# BLE_SCH_Rev1.net
KiCad netlist of a schematic drawn in Altium Designer
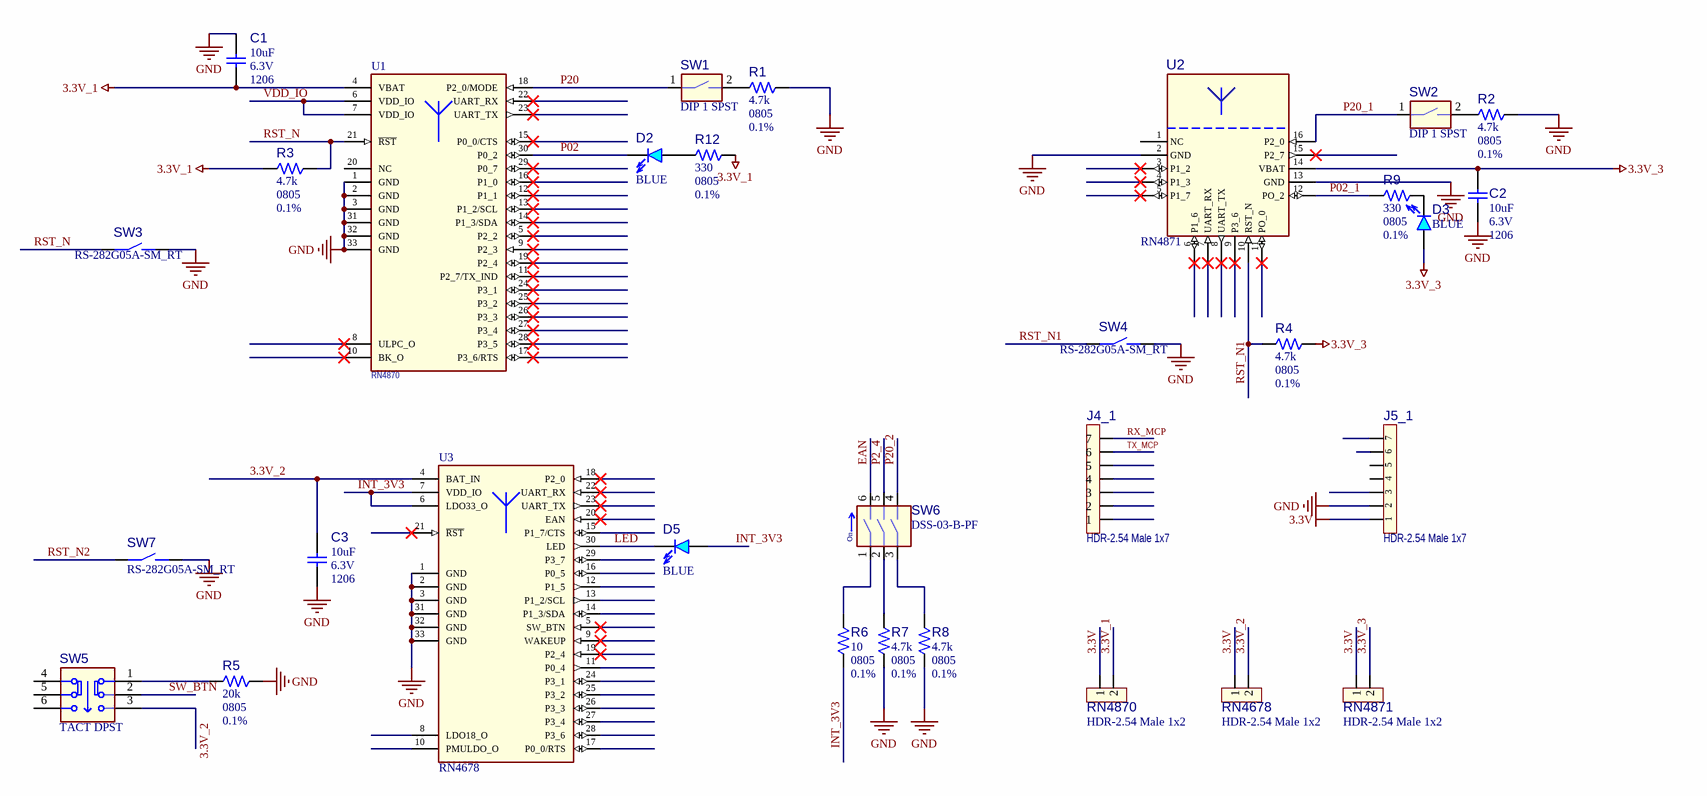
[diagram p0: BLE_SCH_Rev1.SchDoc]

(export (version "E")
  (design (tool "Eeschema 10.0.6"))
  (components
    (comp (ref "C1")
      (value "10uF")
      (footprint "CAP_C_1206")
      (fields
        (field (name "VOLTAGE") "6.3V")
        (field (name "PACKAGE") "1206")
        (field (name "TOLERANCE") "20%")
        (field (name "Comment") "Capacitor NP")
      )
      (libsource (lib "MCHP-CDB") (part "Capacitor NP"))
    )
    (comp (ref "C2")
      (value "10uF")
      (footprint "CAP_C_1206")
      (fields
        (field (name "VOLTAGE") "6.3V")
        (field (name "PACKAGE") "1206")
        (field (name "TOLERANCE") "20%")
        (field (name "Comment") "Capacitor NP")
      )
      (libsource (lib "MCHP-CDB") (part "Capacitor NP"))
    )
    (comp (ref "C3")
      (value "10uF")
      (footprint "CAP_C_1206")
      (fields
        (field (name "VOLTAGE") "6.3V")
        (field (name "PACKAGE") "1206")
        (field (name "TOLERANCE") "20%")
        (field (name "Comment") "Capacitor NP")
      )
      (libsource (lib "MCHP-CDB") (part "Capacitor NP"))
    )
    (comp (ref "D2")
      (value "BLUE")
      (footprint "LED_0805_BLUE")
      (description "LED")
      (fields (field (name "Comment") "LED_blue"))
      (libsource (lib "MCHP-CDB") (part "LED_blue"))
    )
    (comp (ref "D3")
      (value "BLUE")
      (footprint "LED_0805_BLUE")
      (description "LED")
      (fields (field (name "Comment") "LED_blue"))
      (libsource (lib "MCHP-CDB") (part "LED_blue"))
    )
    (comp (ref "D5")
      (value "BLUE")
      (footprint "LED_0805_BLUE")
      (description "LED")
      (fields (field (name "Comment") "LED_blue"))
      (libsource (lib "MCHP-CDB") (part "LED_blue"))
    )
    (comp (ref "J4_1")
      (value "HDR-2.54 Male 1x7")
      (footprint "HDR_M_2.54_1x7")
      (fields (field (name "Comment") "Header 1x7"))
      (libsource (lib "MCHP-CDB") (part "Header 1x7"))
    )
    (comp (ref "J5_1")
      (value "HDR-2.54 Male 1x7")
      (footprint "HDR_M_2.54_1x7")
      (fields (field (name "Comment") "Header 1x7"))
      (libsource (lib "") (part "Header 1x7_1"))
    )
    (comp (ref "R1")
      (value "4.7k")
      (footprint "RES_C_0805")
      (description "Resistor")
      (fields (field (name "PACKAGE") "0805") (field (name "TOLERANCE") "0.1%"))
      (libsource (lib "MCHP-CDB") (part "Resistor"))
    )
    (comp (ref "R2")
      (value "4.7k")
      (footprint "RES_C_0805")
      (description "Resistor")
      (fields (field (name "PACKAGE") "0805") (field (name "TOLERANCE") "0.1%"))
      (libsource (lib "MCHP-CDB") (part "Resistor"))
    )
    (comp (ref "R3")
      (value "4.7k")
      (footprint "RES_C_0805")
      (description "Resistor")
      (fields (field (name "PACKAGE") "0805") (field (name "TOLERANCE") "0.1%"))
      (libsource (lib "MCHP-CDB") (part "Resistor"))
    )
    (comp (ref "R4")
      (value "4.7k")
      (footprint "RES_C_0805")
      (description "Resistor")
      (fields (field (name "PACKAGE") "0805") (field (name "TOLERANCE") "0.1%"))
      (libsource (lib "MCHP-CDB") (part "Resistor"))
    )
    (comp (ref "R5")
      (value "20k")
      (footprint "RES_C_0805")
      (description "Resistor")
      (fields (field (name "PACKAGE") "0805") (field (name "TOLERANCE") "0.1%"))
      (libsource (lib "MCHP-CDB") (part "Resistor"))
    )
    (comp (ref "R6")
      (value "10")
      (footprint "RES_C_0805")
      (description "Resistor")
      (fields (field (name "PACKAGE") "0805") (field (name "TOLERANCE") "0.1%"))
      (libsource (lib "MCHP-CDB") (part "Resistor"))
    )
    (comp (ref "R7")
      (value "4.7k")
      (footprint "RES_C_0805")
      (description "Resistor")
      (fields (field (name "PACKAGE") "0805") (field (name "TOLERANCE") "0.1%"))
      (libsource (lib "MCHP-CDB") (part "Resistor"))
    )
    (comp (ref "R8")
      (value "4.7k")
      (footprint "RES_C_0805")
      (description "Resistor")
      (fields (field (name "PACKAGE") "0805") (field (name "TOLERANCE") "0.1%"))
      (libsource (lib "MCHP-CDB") (part "Resistor"))
    )
    (comp (ref "R9")
      (value "330")
      (footprint "RES_C_0805")
      (description "Resistor")
      (fields (field (name "PACKAGE") "0805") (field (name "TOLERANCE") "0.1%"))
      (libsource (lib "MCHP-CDB") (part "Resistor"))
    )
    (comp (ref "R12")
      (value "330")
      (footprint "RES_C_0805")
      (description "Resistor")
      (fields (field (name "PACKAGE") "0805") (field (name "TOLERANCE") "0.1%"))
      (libsource (lib "MCHP-CDB") (part "Resistor"))
    )
    (comp (ref "RN4678")
      (value "HDR-2.54 Male 1x2")
      (footprint "HDR_M_2.54_1x2")
      (fields (field (name "Comment") "Header 1x2") (field (name "OWNER") "Randolph Sobrepena"))
      (libsource (lib "MCHP-CDB") (part "Header 1x2"))
    )
    (comp (ref "RN4870")
      (value "HDR-2.54 Male 1x2")
      (footprint "HDR_M_2.54_1x2")
      (fields (field (name "Comment") "Header 1x2") (field (name "OWNER") "Randolph Sobrepena"))
      (libsource (lib "MCHP-CDB") (part "Header 1x2"))
    )
    (comp (ref "RN4871")
      (value "HDR-2.54 Male 1x2")
      (footprint "HDR_M_2.54_1x2")
      (fields (field (name "Comment") "Header 1x2") (field (name "OWNER") "Randolph Sobrepena"))
      (libsource (lib "MCHP-CDB") (part "Header 1x2"))
    )
    (comp (ref "SW1")
      (value "DIP 1 SPST")
      (footprint "SW_TH_2.54MM X 1 418117270901")
      (description "Switch DIP 1 Pos")
      (fields (field (name "VOLTAGE") "24V") (field (name "OWNER") "Gabor Bihari"))
      (libsource (lib "MCHP-CDB") (part "Switch DIP 1 Pos"))
    )
    (comp (ref "SW2")
      (value "DIP 1 SPST")
      (footprint "SW_TH_2.54MM X 1 418117270901")
      (description "Switch DIP 1 Pos")
      (fields (field (name "VOLTAGE") "24V") (field (name "OWNER") "Gabor Bihari"))
      (libsource (lib "MCHP-CDB") (part "Switch DIP 1 Pos"))
    )
    (comp (ref "SW3")
      (value "RS-282G05A-SM_RT")
      (footprint "SW_TACT_SMD_CK_RS-282G05A3-SM RT")
      (description "Switch")
      (fields
        (field (name "VOLTAGE") "12V")
        (field (name "Comment") "Switch 2 Pin")
        (field (name "OWNER") "Gabor Bihari")
      )
      (libsource (lib "MCHP-CDB") (part "Switch 2 Pin"))
    )
    (comp (ref "SW4")
      (value "RS-282G05A-SM_RT")
      (footprint "SW_TACT_SMD_CK_RS-282G05A3-SM RT")
      (description "Switch")
      (fields
        (field (name "VOLTAGE") "12V")
        (field (name "Comment") "Switch 2 Pin")
        (field (name "OWNER") "Gabor Bihari")
      )
      (libsource (lib "MCHP-CDB") (part "Switch 2 Pin"))
    )
    (comp (ref "SW5")
      (value "TACT DPST")
      (footprint "SW_TACT_TH_PS07-22L-PF")
      (description "PS-5177")
      (fields (field (name "Comment") "Switch on-off 6 Pin") (field (name "OWNER") "Duane Burt"))
      (libsource (lib "MCHP-CDB") (part "Switch on-off 6 Pin"))
    )
    (comp (ref "SW6")
      (value "DSS-03-B-PF")
      (footprint "SW_TH_2.54MM X 3 Omron")
      (description "Switch DIP")
      (fields (field (name "Comment") "Switch DIP 3 Pos") (field (name "OWNER") "Duane Burt"))
      (libsource (lib "MCHP-CDB") (part "Switch DIP 3 Pos"))
    )
    (comp (ref "SW7")
      (value "RS-282G05A-SM_RT")
      (footprint "SW_TACT_SMD_CK_RS-282G05A3-SM RT")
      (description "Switch")
      (fields
        (field (name "VOLTAGE") "12V")
        (field (name "Comment") "Switch 2 Pin")
        (field (name "OWNER") "Gabor Bihari")
      )
      (libsource (lib "MCHP-CDB") (part "Switch 2 Pin"))
    )
    (comp (ref "U1")
      (value "RN4870")
      (footprint "MOD_BM70BLES1FC2")
      (fields (field (name "Comment") "MODULE BM70BLES1FC2") (field (name "OWNER") "Jojie Batislaon"))
      (libsource (lib "MCHP-CDB") (part "MODULE BM70BLES1FC2"))
    )
    (comp (ref "U2")
      (value "RN4871")
      (footprint "RN4871 MODULE-16")
      (fields (field (name "Comment") "RN4871 MODULE") (field (name "OWNER") "Octavian Stroe"))
      (libsource (lib "MCHP-CDB") (part "RN4871 MODULE"))
    )
    (comp (ref "U3")
      (value "RN4678")
      (footprint "MOD_BM78SPPS5xC2")
      (fields (field (name "Comment") "MODULE BM78SPPS5xC2") (field (name "OWNER") "Jojie Batislaon"))
      (libsource (lib "MCHP-CDB") (part "MODULE BM78SPPS5xC2"))
    )
  )
  (nets
    (net (code "1") (name "/3.3V_2") (class "Default")
      (node (ref "C3") (pin "2") (pinfunction "2_2") (pintype "passive"))
      (node (ref "RN4678") (pin "2") (pinfunction "2_2") (pintype "passive"))
      (node (ref "SW5") (pin "3") (pinfunction "3_3") (pintype "passive"))
      (node (ref "U3") (pin "4") (pinfunction "BAT_IN_4") (pintype "power_in"))
    )
    (net (code "2") (name "/EAN") (class "Default")
      (node (ref "SW6") (pin "6") (pinfunction "6_6") (pintype "passive"))
    )
    (net (code "3") (name "/INT_3V3") (class "Default")
      (node (ref "D5") (pin "1") (pinfunction "A_1") (pintype "passive"))
      (node (ref "R6") (pin "2") (pinfunction "2_2") (pintype "passive"))
      (node (ref "U3") (pin "6") (pinfunction "LDO33_O_6") (pintype "power_in"))
      (node (ref "U3") (pin "7") (pinfunction "VDD_IO_7") (pintype "power_in"))
    )
    (net (code "4") (name "/LED") (class "Default")
      (node (ref "D5") (pin "2") (pinfunction "K_2") (pintype "passive"))
      (node (ref "U3") (pin "30") (pinfunction "LED_30") (pintype "output"))
    )
    (net (code "5") (name "/P02") (class "Default")
      (node (ref "D2") (pin "2") (pinfunction "K_2") (pintype "passive"))
      (node (ref "U1") (pin "30") (pinfunction "P0_2_30") (pintype "bidirectional"))
    )
    (net (code "6") (name "/P02_1") (class "Default")
      (node (ref "R9") (pin "1") (pinfunction "1_1") (pintype "passive"))
      (node (ref "U2") (pin "12") (pinfunction "PO_2_12") (pintype "bidirectional"))
    )
    (net (code "7") (name "/P2_4") (class "Default")
      (node (ref "SW6") (pin "5") (pinfunction "5_5") (pintype "passive"))
    )
    (net (code "8") (name "/P20") (class "Default")
      (node (ref "SW1") (pin "1") (pinfunction "1_1") (pintype "passive"))
      (node (ref "U1") (pin "18") (pinfunction "P2_0/MODE_18") (pintype "input"))
    )
    (net (code "9") (name "/P20_1") (class "Default")
      (node (ref "SW2") (pin "1") (pinfunction "1_1") (pintype "passive"))
      (node (ref "U2") (pin "16") (pinfunction "P2_0_16") (pintype "input"))
    )
    (net (code "10") (name "/P20_2") (class "Default")
      (node (ref "SW6") (pin "4") (pinfunction "4_4") (pintype "passive"))
    )
    (net (code "11") (name "/RST_N") (class "Default")
      (node (ref "R3") (pin "1") (pinfunction "1_1") (pintype "passive"))
      (node (ref "SW3") (pin "1") (pinfunction "1_1") (pintype "passive"))
      (node (ref "U1") (pin "21") (pinfunction "~{RST}_21") (pintype "input"))
    )
    (net (code "12") (name "/RST_N1") (class "Default")
      (node (ref "R4") (pin "2") (pinfunction "2_2") (pintype "passive"))
      (node (ref "SW4") (pin "1") (pinfunction "1_1") (pintype "passive"))
      (node (ref "U2") (pin "10") (pinfunction "RST_N_10") (pintype "input"))
    )
    (net (code "13") (name "/RST_N2") (class "Default")
      (node (ref "SW7") (pin "1") (pinfunction "1_1") (pintype "passive"))
    )
    (net (code "14") (name "/RX_MCP") (class "Default")
      (node (ref "J4_1") (pin "7") (pinfunction "7_7") (pintype "passive"))
    )
    (net (code "15") (name "/SW_BTN") (class "Default")
      (node (ref "SW5") (pin "2") (pinfunction "2_2") (pintype "passive"))
    )
    (net (code "16") (name "/TX_MCP") (class "Default")
      (node (ref "J4_1") (pin "6") (pinfunction "6_6") (pintype "passive"))
    )
    (net (code "17") (name "/VDD_IO") (class "Default")
      (node (ref "U1") (pin "6") (pinfunction "VDD_IO_6") (pintype "power_in"))
      (node (ref "U1") (pin "7") (pinfunction "VDD_IO_7") (pintype "power_in"))
    )
    (net (code "18") (name "3.3V") (class "Default")
      (node (ref "J5_1") (pin "1") (pinfunction "1_1") (pintype "passive"))
      (node (ref "RN4678") (pin "1") (pinfunction "1_1") (pintype "passive"))
      (node (ref "RN4870") (pin "1") (pinfunction "1_1") (pintype "passive"))
      (node (ref "RN4871") (pin "1") (pinfunction "1_1") (pintype "passive"))
    )
    (net (code "19") (name "3.3V_1") (class "Default")
      (node (ref "C1") (pin "1") (pinfunction "1_1") (pintype "passive"))
      (node (ref "R12") (pin "2") (pinfunction "2_2") (pintype "passive"))
      (node (ref "R3") (pin "2") (pinfunction "2_2") (pintype "passive"))
      (node (ref "RN4870") (pin "2") (pinfunction "2_2") (pintype "passive"))
      (node (ref "U1") (pin "4") (pinfunction "VBAT_4") (pintype "power_in"))
    )
    (net (code "20") (name "3.3V_3") (class "Default")
      (node (ref "C2") (pin "1") (pinfunction "1_1") (pintype "passive"))
      (node (ref "D3") (pin "1") (pinfunction "A_1") (pintype "passive"))
      (node (ref "R4") (pin "1") (pinfunction "1_1") (pintype "passive"))
      (node (ref "RN4871") (pin "2") (pinfunction "2_2") (pintype "passive"))
      (node (ref "U2") (pin "14") (pinfunction "VBAT_14") (pintype "power_in"))
    )
    (net (code "21") (name "GND") (class "Default")
      (node (ref "C1") (pin "2") (pinfunction "2_2") (pintype "passive"))
      (node (ref "C2") (pin "2") (pinfunction "2_2") (pintype "passive"))
      (node (ref "C3") (pin "1") (pinfunction "1_1") (pintype "passive"))
      (node (ref "J5_1") (pin "2") (pinfunction "2_2") (pintype "passive"))
      (node (ref "R1") (pin "1") (pinfunction "1_1") (pintype "passive"))
      (node (ref "R2") (pin "1") (pinfunction "1_1") (pintype "passive"))
      (node (ref "R5") (pin "1") (pinfunction "1_1") (pintype "passive"))
      (node (ref "R7") (pin "2") (pinfunction "2_2") (pintype "passive"))
      (node (ref "R8") (pin "2") (pinfunction "2_2") (pintype "passive"))
      (node (ref "SW3") (pin "2") (pinfunction "2_2") (pintype "passive"))
      (node (ref "SW4") (pin "2") (pinfunction "2_2") (pintype "passive"))
      (node (ref "SW7") (pin "2") (pinfunction "2_2") (pintype "passive"))
      (node (ref "U1") (pin "1") (pinfunction "GND_1") (pintype "power_in"))
      (node (ref "U1") (pin "2") (pinfunction "GND_2") (pintype "power_in"))
      (node (ref "U1") (pin "3") (pinfunction "GND_3") (pintype "power_in"))
      (node (ref "U1") (pin "31") (pinfunction "GND_31") (pintype "power_in"))
      (node (ref "U1") (pin "32") (pinfunction "GND_32") (pintype "power_in"))
      (node (ref "U1") (pin "33") (pinfunction "GND_33") (pintype "power_in"))
      (node (ref "U2") (pin "13") (pinfunction "GND_13") (pintype "power_in"))
      (node (ref "U2") (pin "2") (pinfunction "GND_2") (pintype "power_in"))
      (node (ref "U3") (pin "1") (pinfunction "GND_1") (pintype "power_in"))
      (node (ref "U3") (pin "2") (pinfunction "GND_2") (pintype "power_in"))
      (node (ref "U3") (pin "3") (pinfunction "GND_3") (pintype "power_in"))
      (node (ref "U3") (pin "31") (pinfunction "GND_31") (pintype "power_in"))
      (node (ref "U3") (pin "32") (pinfunction "GND_32") (pintype "power_in"))
      (node (ref "U3") (pin "33") (pinfunction "GND_33") (pintype "power_in"))
    )
    (net (code "22") (name "Net-(D2-A)") (class "Default")
      (node (ref "D2") (pin "1") (pinfunction "A_1") (pintype "passive"))
      (node (ref "R12") (pin "1") (pinfunction "1_1") (pintype "passive"))
    )
    (net (code "23") (name "Net-(D3-K)") (class "Default")
      (node (ref "D3") (pin "2") (pinfunction "K_2") (pintype "passive"))
      (node (ref "R9") (pin "2") (pinfunction "2_2") (pintype "passive"))
    )
    (net (code "24") (name "Net-(R1-Pad2)") (class "Default")
      (node (ref "R1") (pin "2") (pinfunction "2_2") (pintype "passive"))
      (node (ref "SW1") (pin "2") (pinfunction "2_2") (pintype "passive"))
    )
    (net (code "25") (name "Net-(R2-Pad2)") (class "Default")
      (node (ref "R2") (pin "2") (pinfunction "2_2") (pintype "passive"))
      (node (ref "SW2") (pin "2") (pinfunction "2_2") (pintype "passive"))
    )
    (net (code "26") (name "Net-(R5-Pad2)") (class "Default")
      (node (ref "R5") (pin "2") (pinfunction "2_2") (pintype "passive"))
      (node (ref "SW5") (pin "1") (pinfunction "1_1") (pintype "passive"))
    )
    (net (code "27") (name "Net-(R6-Pad1)") (class "Default")
      (node (ref "R6") (pin "1") (pinfunction "1_1") (pintype "passive"))
      (node (ref "SW6") (pin "1") (pinfunction "1_1") (pintype "passive"))
    )
    (net (code "28") (name "Net-(R7-Pad1)") (class "Default")
      (node (ref "R7") (pin "1") (pinfunction "1_1") (pintype "passive"))
      (node (ref "SW6") (pin "2") (pinfunction "2_2") (pintype "passive"))
    )
    (net (code "29") (name "Net-(R8-Pad1)") (class "Default")
      (node (ref "R8") (pin "1") (pinfunction "1_1") (pintype "passive"))
      (node (ref "SW6") (pin "3") (pinfunction "3_3") (pintype "passive"))
    )
    (net (code "30") (name "unconnected-(J4_1-Pad1)") (class "Default")
      (node (ref "J4_1") (pin "1") (pinfunction "1_1") (pintype "passive"))
    )
    (net (code "31") (name "unconnected-(J4_1-Pad2)") (class "Default")
      (node (ref "J4_1") (pin "2") (pinfunction "2_2") (pintype "passive"))
    )
    (net (code "32") (name "unconnected-(J4_1-Pad3)") (class "Default")
      (node (ref "J4_1") (pin "3") (pinfunction "3_3") (pintype "passive"))
    )
    (net (code "33") (name "unconnected-(J4_1-Pad4)") (class "Default")
      (node (ref "J4_1") (pin "4") (pinfunction "4_4") (pintype "passive"))
    )
    (net (code "34") (name "unconnected-(J4_1-Pad5)") (class "Default")
      (node (ref "J4_1") (pin "5") (pinfunction "5_5") (pintype "passive"))
    )
    (net (code "35") (name "unconnected-(J5_1-Pad3)") (class "Default")
      (node (ref "J5_1") (pin "3") (pinfunction "3_3") (pintype "passive"))
    )
    (net (code "36") (name "unconnected-(J5_1-Pad4)") (class "Default")
      (node (ref "J5_1") (pin "4") (pinfunction "4_4") (pintype "passive"))
    )
    (net (code "37") (name "unconnected-(J5_1-Pad5)") (class "Default")
      (node (ref "J5_1") (pin "5") (pinfunction "5_5") (pintype "passive"))
    )
    (net (code "38") (name "unconnected-(J5_1-Pad6)") (class "Default")
      (node (ref "J5_1") (pin "6") (pinfunction "6_6") (pintype "passive"))
    )
    (net (code "39") (name "unconnected-(J5_1-Pad7)") (class "Default")
      (node (ref "J5_1") (pin "7") (pinfunction "7_7") (pintype "passive"))
    )
    (net (code "40") (name "unconnected-(SW5-Pad4)") (class "Default")
      (node (ref "SW5") (pin "4") (pinfunction "4_4") (pintype "passive"))
    )
    (net (code "41") (name "unconnected-(SW5-Pad5)") (class "Default")
      (node (ref "SW5") (pin "5") (pinfunction "5_5") (pintype "passive"))
    )
    (net (code "42") (name "unconnected-(SW5-Pad6)") (class "Default")
      (node (ref "SW5") (pin "6") (pinfunction "6_6") (pintype "passive"))
    )
    (net (code "43") (name "unconnected-(U1-BK_O-Pad10)") (class "Default")
      (node (ref "U1") (pin "10") (pinfunction "BK_O_10") (pintype "passive+no_connect"))
    )
    (net (code "44") (name "unconnected-(U1-NC-Pad20)") (class "Default")
      (node (ref "U1") (pin "20") (pinfunction "NC_20") (pintype "passive"))
    )
    (net (code "45") (name "unconnected-(U1-P0_0{slash}CTS-Pad15)") (class "Default")
      (node (ref "U1") (pin "15") (pinfunction "P0_0/CTS_15") (pintype "bidirectional+no_connect"))
    )
    (net (code "46") (name "unconnected-(U1-P0_7-Pad29)") (class "Default")
      (node (ref "U1") (pin "29") (pinfunction "P0_7_29") (pintype "bidirectional+no_connect"))
    )
    (net (code "47") (name "unconnected-(U1-P1_0-Pad16)") (class "Default")
      (node (ref "U1") (pin "16") (pinfunction "P1_0_16") (pintype "bidirectional+no_connect"))
    )
    (net (code "48") (name "unconnected-(U1-P1_1-Pad12)") (class "Default")
      (node (ref "U1") (pin "12") (pinfunction "P1_1_12") (pintype "bidirectional+no_connect"))
    )
    (net (code "49") (name "unconnected-(U1-P1_2{slash}SCL-Pad13)") (class "Default")
      (node (ref "U1") (pin "13") (pinfunction "P1_2/SCL_13") (pintype "bidirectional+no_connect"))
    )
    (net (code "50") (name "unconnected-(U1-P1_3{slash}SDA-Pad14)") (class "Default")
      (node (ref "U1") (pin "14") (pinfunction "P1_3/SDA_14") (pintype "bidirectional+no_connect"))
    )
    (net (code "51") (name "unconnected-(U1-P2_2-Pad5)") (class "Default")
      (node (ref "U1") (pin "5") (pinfunction "P2_2_5") (pintype "bidirectional+no_connect"))
    )
    (net (code "52") (name "unconnected-(U1-P2_3-Pad9)") (class "Default")
      (node (ref "U1") (pin "9") (pinfunction "P2_3_9") (pintype "input+no_connect"))
    )
    (net (code "53") (name "unconnected-(U1-P2_4-Pad19)") (class "Default")
      (node (ref "U1") (pin "19") (pinfunction "P2_4_19") (pintype "bidirectional+no_connect"))
    )
    (net (code "54") (name "unconnected-(U1-P2_7{slash}TX_IND-Pad11)") (class "Default")
      (node (ref "U1") (pin "11") (pinfunction "P2_7/TX_IND_11") (pintype "bidirectional+no_connect"))
    )
    (net (code "55") (name "unconnected-(U1-P3_1-Pad24)") (class "Default")
      (node (ref "U1") (pin "24") (pinfunction "P3_1_24") (pintype "bidirectional+no_connect"))
    )
    (net (code "56") (name "unconnected-(U1-P3_2-Pad25)") (class "Default")
      (node (ref "U1") (pin "25") (pinfunction "P3_2_25") (pintype "bidirectional+no_connect"))
    )
    (net (code "57") (name "unconnected-(U1-P3_3-Pad26)") (class "Default")
      (node (ref "U1") (pin "26") (pinfunction "P3_3_26") (pintype "bidirectional+no_connect"))
    )
    (net (code "58") (name "unconnected-(U1-P3_4-Pad27)") (class "Default")
      (node (ref "U1") (pin "27") (pinfunction "P3_4_27") (pintype "bidirectional+no_connect"))
    )
    (net (code "59") (name "unconnected-(U1-P3_5-Pad28)") (class "Default")
      (node (ref "U1") (pin "28") (pinfunction "P3_5_28") (pintype "bidirectional+no_connect"))
    )
    (net (code "60") (name "unconnected-(U1-P3_6{slash}RTS-Pad17)") (class "Default")
      (node (ref "U1") (pin "17") (pinfunction "P3_6/RTS_17") (pintype "bidirectional+no_connect"))
    )
    (net (code "61") (name "unconnected-(U1-UART_RX-Pad22)") (class "Default")
      (node (ref "U1") (pin "22") (pinfunction "UART_RX_22") (pintype "input+no_connect"))
    )
    (net (code "62") (name "unconnected-(U1-UART_TX-Pad23)") (class "Default")
      (node (ref "U1") (pin "23") (pinfunction "UART_TX_23") (pintype "output+no_connect"))
    )
    (net (code "63") (name "unconnected-(U1-ULPC_O-Pad8)") (class "Default")
      (node (ref "U1") (pin "8") (pinfunction "ULPC_O_8") (pintype "passive+no_connect"))
    )
    (net (code "64") (name "unconnected-(U2-NC-Pad1)") (class "Default")
      (node (ref "U2") (pin "1") (pinfunction "NC_1") (pintype "passive"))
    )
    (net (code "65") (name "unconnected-(U2-P1_2-Pad3)") (class "Default")
      (node (ref "U2") (pin "3") (pinfunction "P1_2_3") (pintype "bidirectional+no_connect"))
    )
    (net (code "66") (name "unconnected-(U2-P1_3-Pad4)") (class "Default")
      (node (ref "U2") (pin "4") (pinfunction "P1_3_4") (pintype "bidirectional+no_connect"))
    )
    (net (code "67") (name "unconnected-(U2-P1_6-Pad6)") (class "Default")
      (node (ref "U2") (pin "6") (pinfunction "P1_6_6") (pintype "bidirectional+no_connect"))
    )
    (net (code "68") (name "unconnected-(U2-P1_7-Pad5)") (class "Default")
      (node (ref "U2") (pin "5") (pinfunction "P1_7_5") (pintype "bidirectional+no_connect"))
    )
    (net (code "69") (name "unconnected-(U2-P2_7-Pad15)") (class "Default")
      (node (ref "U2") (pin "15") (pinfunction "P2_7_15") (pintype "output+no_connect"))
    )
    (net (code "70") (name "unconnected-(U2-P3_6-Pad9)") (class "Default")
      (node (ref "U2") (pin "9") (pinfunction "P3_6_9") (pintype "power_in+no_connect"))
    )
    (net (code "71") (name "unconnected-(U2-PO_0-Pad11)") (class "Default")
      (node (ref "U2") (pin "11") (pinfunction "PO_0_11") (pintype "bidirectional+no_connect"))
    )
    (net (code "72") (name "unconnected-(U2-UART_RX-Pad7)") (class "Default")
      (node (ref "U2") (pin "7") (pinfunction "UART_RX_7") (pintype "input+no_connect"))
    )
    (net (code "73") (name "unconnected-(U2-UART_TX-Pad8)") (class "Default")
      (node (ref "U2") (pin "8") (pinfunction "UART_TX_8") (pintype "output+no_connect"))
    )
    (net (code "74") (name "unconnected-(U3-EAN-Pad20)") (class "Default")
      (node (ref "U3") (pin "20") (pinfunction "EAN_20") (pintype "input+no_connect"))
    )
    (net (code "75") (name "unconnected-(U3-LDO18_O-Pad8)") (class "Default")
      (node (ref "U3") (pin "8") (pinfunction "LDO18_O_8") (pintype "passive"))
    )
    (net (code "76") (name "unconnected-(U3-P0_0{slash}RTS-Pad17)") (class "Default")
      (node (ref "U3") (pin "17") (pinfunction "P0_0/RTS_17") (pintype "bidirectional"))
    )
    (net (code "77") (name "unconnected-(U3-P0_4-Pad11)") (class "Default")
      (node (ref "U3") (pin "11") (pinfunction "P0_4_11") (pintype "output"))
    )
    (net (code "78") (name "unconnected-(U3-P0_5-Pad16)") (class "Default")
      (node (ref "U3") (pin "16") (pinfunction "P0_5_16") (pintype "bidirectional"))
    )
    (net (code "79") (name "unconnected-(U3-P1_2{slash}SCL-Pad13)") (class "Default")
      (node (ref "U3") (pin "13") (pinfunction "P1_2/SCL_13") (pintype "output"))
    )
    (net (code "80") (name "unconnected-(U3-P1_3{slash}SDA-Pad14)") (class "Default")
      (node (ref "U3") (pin "14") (pinfunction "P1_3/SDA_14") (pintype "bidirectional"))
    )
    (net (code "81") (name "unconnected-(U3-P1_5-Pad12)") (class "Default")
      (node (ref "U3") (pin "12") (pinfunction "P1_5_12") (pintype "output"))
    )
    (net (code "82") (name "unconnected-(U3-P1_7{slash}CTS-Pad15)") (class "Default")
      (node (ref "U3") (pin "15") (pinfunction "P1_7/CTS_15") (pintype "bidirectional"))
    )
    (net (code "83") (name "unconnected-(U3-P2_0-Pad18)") (class "Default")
      (node (ref "U3") (pin "18") (pinfunction "P2_0_18") (pintype "input+no_connect"))
    )
    (net (code "84") (name "unconnected-(U3-P2_4-Pad19)") (class "Default")
      (node (ref "U3") (pin "19") (pinfunction "P2_4_19") (pintype "input+no_connect"))
    )
    (net (code "85") (name "unconnected-(U3-P3_1-Pad24)") (class "Default")
      (node (ref "U3") (pin "24") (pinfunction "P3_1_24") (pintype "bidirectional"))
    )
    (net (code "86") (name "unconnected-(U3-P3_2-Pad25)") (class "Default")
      (node (ref "U3") (pin "25") (pinfunction "P3_2_25") (pintype "bidirectional"))
    )
    (net (code "87") (name "unconnected-(U3-P3_3-Pad26)") (class "Default")
      (node (ref "U3") (pin "26") (pinfunction "P3_3_26") (pintype "bidirectional"))
    )
    (net (code "88") (name "unconnected-(U3-P3_4-Pad27)") (class "Default")
      (node (ref "U3") (pin "27") (pinfunction "P3_4_27") (pintype "bidirectional"))
    )
    (net (code "89") (name "unconnected-(U3-P3_6-Pad28)") (class "Default")
      (node (ref "U3") (pin "28") (pinfunction "P3_6_28") (pintype "bidirectional"))
    )
    (net (code "90") (name "unconnected-(U3-P3_7-Pad29)") (class "Default")
      (node (ref "U3") (pin "29") (pinfunction "P3_7_29") (pintype "bidirectional"))
    )
    (net (code "91") (name "unconnected-(U3-PMULDO_O-Pad10)") (class "Default")
      (node (ref "U3") (pin "10") (pinfunction "PMULDO_O_10") (pintype "passive"))
    )
    (net (code "92") (name "unconnected-(U3-SW_BTN-Pad5)") (class "Default")
      (node (ref "U3") (pin "5") (pinfunction "SW_BTN_5") (pintype "input+no_connect"))
    )
    (net (code "93") (name "unconnected-(U3-UART_RX-Pad22)") (class "Default")
      (node (ref "U3") (pin "22") (pinfunction "UART_RX_22") (pintype "input+no_connect"))
    )
    (net (code "94") (name "unconnected-(U3-UART_TX-Pad23)") (class "Default")
      (node (ref "U3") (pin "23") (pinfunction "UART_TX_23") (pintype "output+no_connect"))
    )
    (net (code "95") (name "unconnected-(U3-WAKEUP-Pad9)") (class "Default")
      (node (ref "U3") (pin "9") (pinfunction "WAKEUP_9") (pintype "input+no_connect"))
    )
    (net (code "96") (name "unconnected-(U3-~{RST}-Pad21)") (class "Default")
      (node (ref "U3") (pin "21") (pinfunction "~{RST}_21") (pintype "input+no_connect"))
    )
  )
)
